# Doorbell.net
KiCad netlist of a schematic drawn in EAGLE
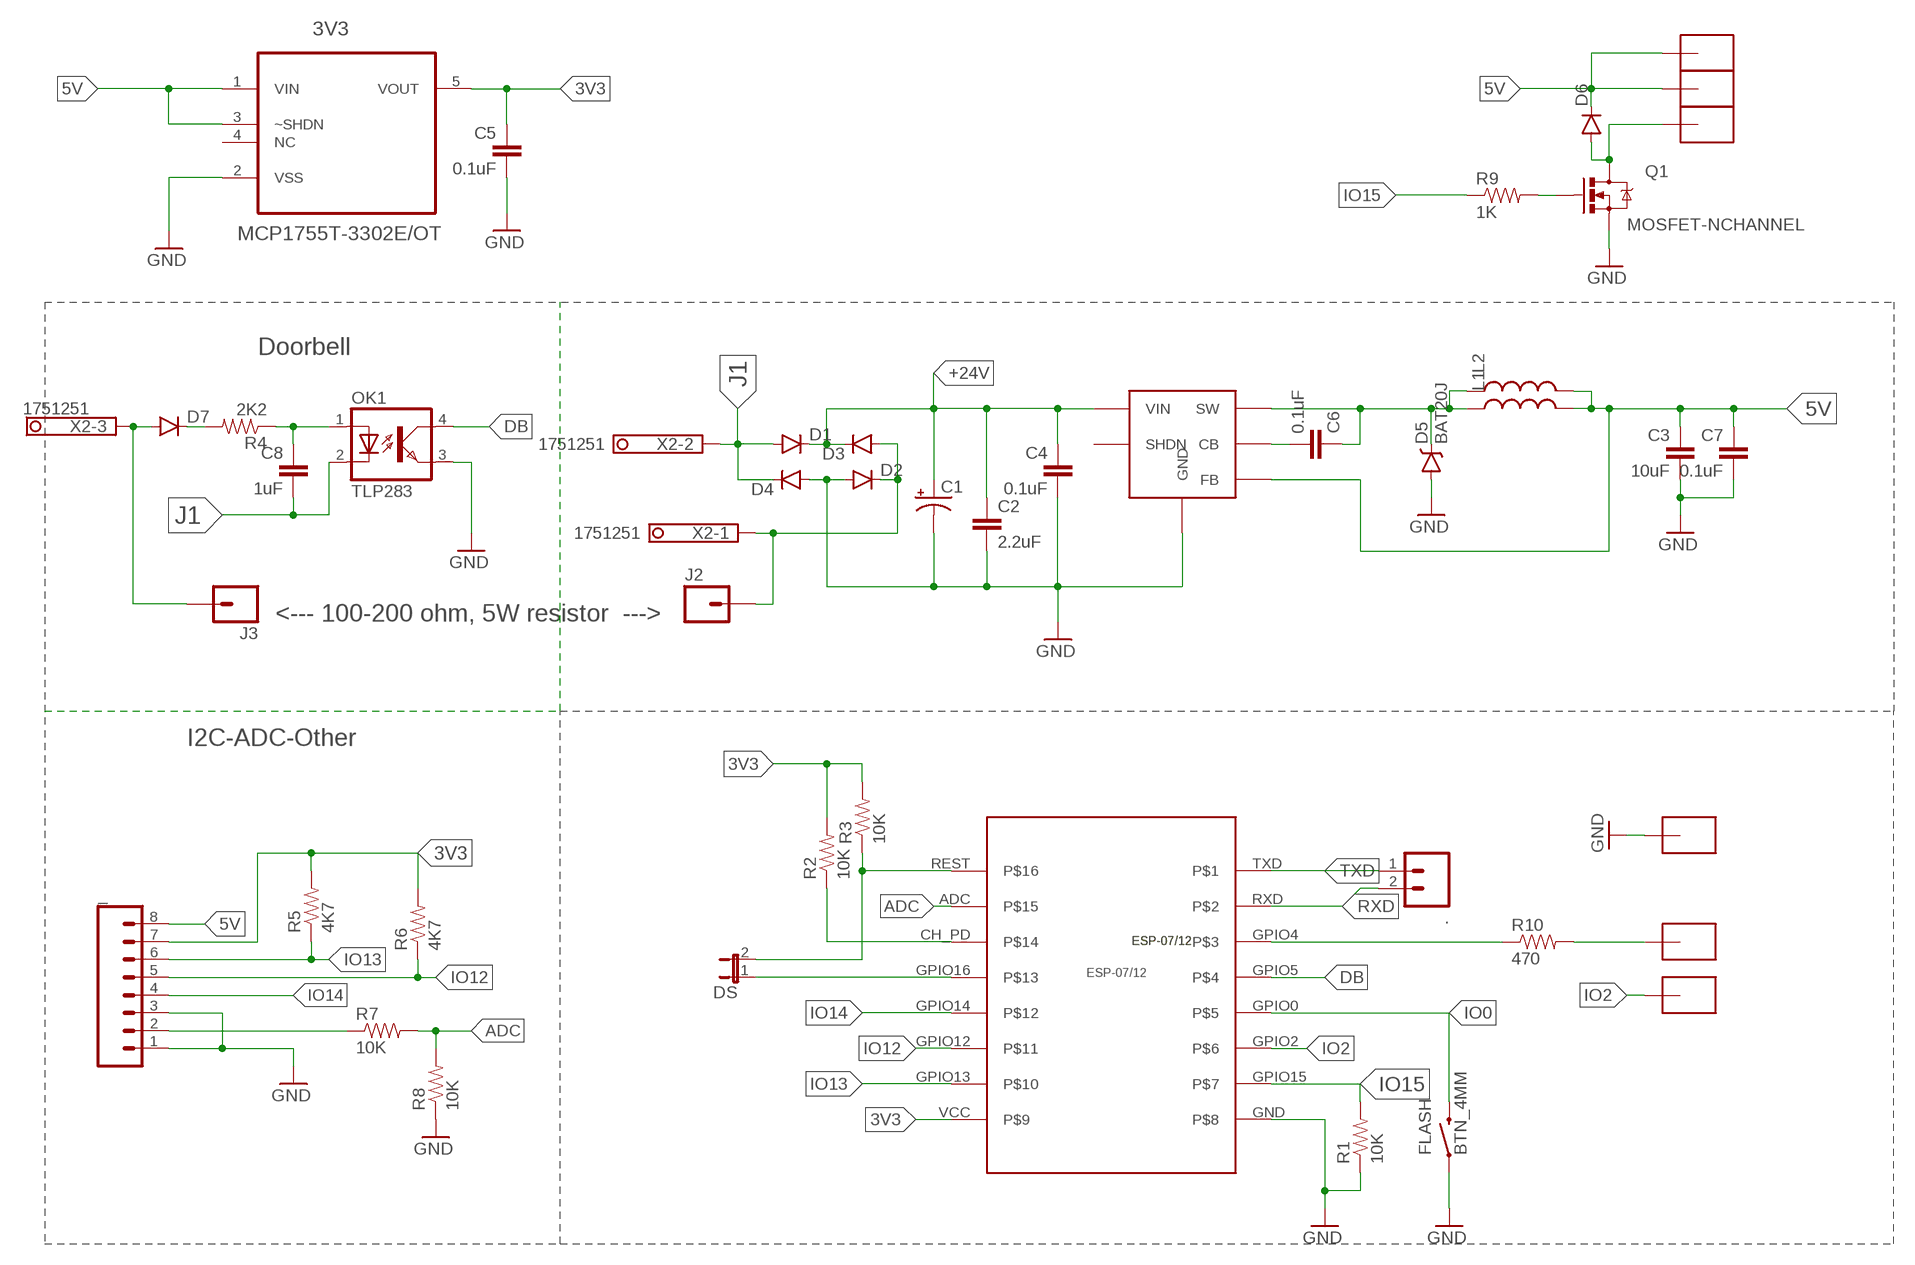
[diagram p0: schematic, sheet 1]

(export (version "E")
  (design (tool "Eeschema 10.0.6"))
  (components
    (comp (ref ".")
      (value "M02PTH")
      (footprint "eagle-import:1X02")
      (libsource (lib "eagle-import") (part "M02PTH"))
    )
    (comp (ref "3V3")
      (value "MCP1755T-3302E/OT")
      (footprint "eagle-import:SOT95P270X145-5N")
      (fields (field (name "MPN") "MCP1801T-3302I/OT"))
      (libsource (lib "eagle-import") (part "MCP1801T-3302I/OT"))
    )
    (comp (ref "C1")
      (value "CAP_POLPTH4")
      (footprint "eagle-import:CPOL-RADIAL-1000UF-25V")
      (libsource (lib "eagle-import") (part "CAP_POLPTH4"))
    )
    (comp (ref "C2")
      (value "2.2uF")
      (footprint "eagle-import:1206")
      (libsource (lib "eagle-import") (part "SparkFun-Passives_CAP1206"))
    )
    (comp (ref "C3")
      (value "10uF")
      (footprint "eagle-import:0805-CAP")
      (libsource (lib "eagle-import") (part "CAP"))
    )
    (comp (ref "C4")
      (value "0.1uF")
      (footprint "eagle-import:0805-CAP")
      (libsource (lib "eagle-import") (part "CAP"))
    )
    (comp (ref "C5")
      (value "0.1uF")
      (footprint "eagle-import:0805-CAP")
      (libsource (lib "eagle-import") (part "CAP"))
    )
    (comp (ref "C6")
      (value "0.1uF")
      (footprint "eagle-import:0805-CAP")
      (libsource (lib "eagle-import") (part "CAP"))
    )
    (comp (ref "C7")
      (value "0.1uF")
      (footprint "eagle-import:0805-CAP")
      (libsource (lib "eagle-import") (part "CAP"))
    )
    (comp (ref "C8")
      (value "1uF")
      (footprint "eagle-import:0805-CAP")
      (libsource (lib "eagle-import") (part "CAP"))
    )
    (comp (ref "D1")
      (value "DIODESOD123")
      (footprint "eagle-import:SOD-123")
      (libsource (lib "eagle-import") (part "DIODESOD123"))
    )
    (comp (ref "D2")
      (value "DIODESOD123")
      (footprint "eagle-import:SOD-123")
      (libsource (lib "eagle-import") (part "DIODESOD123"))
    )
    (comp (ref "D3")
      (value "DIODESOD123")
      (footprint "eagle-import:SOD-123")
      (libsource (lib "eagle-import") (part "DIODESOD123"))
    )
    (comp (ref "D4")
      (value "DIODESOD123")
      (footprint "eagle-import:SOD-123")
      (libsource (lib "eagle-import") (part "DIODESOD123"))
    )
    (comp (ref "D5")
      (value "BAT20J")
      (footprint "eagle-import:SOD-323")
      (libsource (lib "eagle-import") (part "DIODE-SCHOTTKY-BAT20J"))
    )
    (comp (ref "D6")
      (value "DIODESOD123")
      (footprint "eagle-import:SOD-123")
      (libsource (lib "eagle-import") (part "DIODESOD123"))
    )
    (comp (ref "D7")
      (value "DIODESOD123")
      (footprint "eagle-import:SOD-123")
      (libsource (lib "eagle-import") (part "DIODESOD123"))
    )
    (comp (ref "DS")
      (value "JUMPER-2SMD-NO")
      (footprint "eagle-import:SJ_2S-NO")
      (libsource (lib "eagle-import") (part "JUMPER-2SMD-NO"))
    )
    (comp (ref "FLASH")
      (value "BTN_4MM")
      (footprint "eagle-import:BTN_4MM")
      (libsource (lib "eagle-import") (part "BTN_4MM"))
    )
    (comp (ref "J2")
      (value "M01SMDNS")
      (footprint "eagle-import:1X01NS")
      (libsource (lib "eagle-import") (part "M01SMDNS"))
    )
    (comp (ref "J3")
      (value "M01SMDNS")
      (footprint "eagle-import:1X01NS")
      (libsource (lib "eagle-import") (part "M01SMDNS"))
    )
    (comp (ref "L1")
      (value "INDUCTOR0805")
      (footprint "eagle-import:0805")
      (libsource (lib "eagle-import") (part "INDUCTOR0805"))
    )
    (comp (ref "L2")
      (value "INDUCTOR0805")
      (footprint "eagle-import:0805")
      (libsource (lib "eagle-import") (part "INDUCTOR0805"))
    )
    (comp (ref "OK1")
      (value "TLP283")
      (footprint "eagle-import:MINI-FLAT-4")
      (libsource (lib "eagle-import") (part "TLP283"))
    )
    (comp (ref "Q1")
      (value "MOSFET-NCHANNEL")
      (footprint "eagle-import:SOT23-3")
      (libsource (lib "eagle-import") (part "MOSFET-NCHANNELAO3404A"))
    )
    (comp (ref "R1")
      (value "10K")
      (footprint "eagle-import:0805")
      (libsource (lib "eagle-import") (part "RESISTOR0805-RES"))
    )
    (comp (ref "R2")
      (value "10K")
      (footprint "eagle-import:0805")
      (libsource (lib "eagle-import") (part "RESISTOR0805-RES"))
    )
    (comp (ref "R3")
      (value "10K")
      (footprint "eagle-import:0805")
      (libsource (lib "eagle-import") (part "RESISTOR0805-RES"))
    )
    (comp (ref "R4")
      (value "2K2")
      (footprint "eagle-import:0805")
      (libsource (lib "eagle-import") (part "RESISTOR0805-RES"))
    )
    (comp (ref "R5")
      (value "4K7")
      (footprint "eagle-import:0805")
      (libsource (lib "eagle-import") (part "RESISTOR0805-RES"))
    )
    (comp (ref "R6")
      (value "4K7")
      (footprint "eagle-import:0805")
      (libsource (lib "eagle-import") (part "RESISTOR0805-RES"))
    )
    (comp (ref "R7")
      (value "10K")
      (footprint "eagle-import:0805")
      (libsource (lib "eagle-import") (part "RESISTOR0805-RES"))
    )
    (comp (ref "R8")
      (value "10K")
      (footprint "eagle-import:0805")
      (libsource (lib "eagle-import") (part "RESISTOR0805-RES"))
    )
    (comp (ref "R9")
      (value "1K")
      (footprint "eagle-import:0805")
      (libsource (lib "eagle-import") (part "RESISTOR0805-RES"))
    )
    (comp (ref "R10")
      (value "470")
      (footprint "eagle-import:0805")
      (libsource (lib "eagle-import") (part "RESISTOR0805-RES"))
    )
    (comp (ref "U$1")
      (value "ESP-07/12")
      (footprint "eagle-import:ESP-07_12")
      (libsource (lib "eagle-import") (part "ESP-07/12"))
    )
    (comp (ref "U$2")
      (value "SMD-PAD-SM")
      (footprint "eagle-import:SMD-PAD3")
      (libsource (lib "eagle-import") (part "SMD-PAD-SM"))
    )
    (comp (ref "U$3")
      (value "SMD-PAD-SM")
      (footprint "eagle-import:SMD-PAD3")
      (libsource (lib "eagle-import") (part "SMD-PAD-SM"))
    )
    (comp (ref "U$4")
      (value "SMD-PAD-SM")
      (footprint "eagle-import:SMD-PAD3")
      (libsource (lib "eagle-import") (part "SMD-PAD-SM"))
    )
    (comp (ref "U$5")
      (value "SMD-PAD-SM")
      (footprint "eagle-import:SMD-PAD3")
      (libsource (lib "eagle-import") (part "SMD-PAD-SM"))
    )
    (comp (ref "U$6")
      (value "SMD-PAD-SM")
      (footprint "eagle-import:SMD-PAD3")
      (libsource (lib "eagle-import") (part "SMD-PAD-SM"))
    )
    (comp (ref "U$7")
      (value "SMD-PAD-SM")
      (footprint "eagle-import:SMD-PAD3")
      (libsource (lib "eagle-import") (part "SMD-PAD-SM"))
    )
    (comp (ref "VREG")
      (value "LMR16006YQ5DDCRQ1")
      (footprint "eagle-import:SOT-23-6")
      (libsource (lib "eagle-import") (part "LMR16006YQ"))
    )
    (comp (ref "X2")
      (value "1751251")
      (footprint "eagle-import:1751251")
      (libsource (lib "eagle-import") (part "1751251"))
    )
    (comp (ref "_")
      (value "M08SILK_FEMALE_PTH")
      (footprint "eagle-import:1X08")
      (libsource (lib "eagle-import") (part "M08SILK_FEMALE_PTH"))
    )
  )
  (nets
    (net (code "1") (name "+24V") (class "Default")
      (node (ref "C1") (pin "+") (pinfunction "+_+") (pintype "passive"))
      (node (ref "C2") (pin "1") (pinfunction "1_1") (pintype "passive"))
      (node (ref "C4") (pin "1") (pinfunction "1_1") (pintype "passive"))
      (node (ref "D1") (pin "C") (pinfunction "C_C") (pintype "passive"))
      (node (ref "D3") (pin "C") (pinfunction "C_C") (pintype "passive"))
      (node (ref "VREG") (pin "5") (pinfunction "VIN_5") (pintype "input"))
    )
    (net (code "2") (name "3V3") (class "Default")
      (node (ref "3V3") (pin "5") (pinfunction "VOUT_5") (pintype "output"))
      (node (ref "C5") (pin "1") (pinfunction "1_1") (pintype "passive"))
      (node (ref "R2") (pin "2") (pinfunction "2_2") (pintype "passive"))
      (node (ref "R3") (pin "2") (pinfunction "2_2") (pintype "passive"))
      (node (ref "R5") (pin "2") (pinfunction "2_2") (pintype "passive"))
      (node (ref "R6") (pin "2") (pinfunction "2_2") (pintype "passive"))
      (node (ref "U$1") (pin "VCC") (pinfunction "P$9_VCC") (pintype "bidirectional"))
      (node (ref "_") (pin "7") (pinfunction "7_7") (pintype "passive"))
    )
    (net (code "3") (name "5V") (class "Default")
      (node (ref "3V3") (pin "1") (pinfunction "VIN_1") (pintype "power_in"))
      (node (ref "3V3") (pin "3") (pinfunction "~{SHDN}_3") (pintype "input"))
      (node (ref "C3") (pin "1") (pinfunction "1_1") (pintype "passive"))
      (node (ref "C7") (pin "1") (pinfunction "1_1") (pintype "passive"))
      (node (ref "D6") (pin "C") (pinfunction "C_C") (pintype "passive"))
      (node (ref "L1") (pin "2") (pinfunction "2_2") (pintype "passive"))
      (node (ref "L2") (pin "2") (pinfunction "2_2") (pintype "passive"))
      (node (ref "U$3") (pin "P$1") (pinfunction "P$1_P$1") (pintype "bidirectional"))
      (node (ref "U$7") (pin "P$1") (pinfunction "P$1_P$1") (pintype "bidirectional"))
      (node (ref "VREG") (pin "3") (pinfunction "FB_3") (pintype "input"))
      (node (ref "_") (pin "8") (pinfunction "8_8") (pintype "passive"))
    )
    (net (code "4") (name "ADC") (class "Default")
      (node (ref "R7") (pin "2") (pinfunction "2_2") (pintype "passive"))
      (node (ref "R8") (pin "2") (pinfunction "2_2") (pintype "passive"))
      (node (ref "U$1") (pin "ADC") (pinfunction "P$15_ADC") (pintype "bidirectional"))
    )
    (net (code "5") (name "DB") (class "Default")
      (node (ref "OK1") (pin "4") (pinfunction "COL_4") (pintype "passive"))
      (node (ref "U$1") (pin "GPIO5") (pinfunction "P$4_GPIO5") (pintype "bidirectional"))
    )
    (net (code "6") (name "GND") (class "Default")
      (node (ref "3V3") (pin "2") (pinfunction "VSS_2") (pintype "passive"))
      (node (ref "C1") (pin "-") (pinfunction "-_-") (pintype "passive"))
      (node (ref "C2") (pin "2") (pinfunction "2_2") (pintype "passive"))
      (node (ref "C3") (pin "2") (pinfunction "2_2") (pintype "passive"))
      (node (ref "C4") (pin "2") (pinfunction "2_2") (pintype "passive"))
      (node (ref "C5") (pin "2") (pinfunction "2_2") (pintype "passive"))
      (node (ref "C7") (pin "2") (pinfunction "2_2") (pintype "passive"))
      (node (ref "D2") (pin "A") (pinfunction "A_A") (pintype "passive"))
      (node (ref "D4") (pin "A") (pinfunction "A_A") (pintype "passive"))
      (node (ref "D5") (pin "A") (pinfunction "A_A") (pintype "passive"))
      (node (ref "FLASH") (pin "1") (pinfunction "1_1") (pintype "passive"))
      (node (ref "OK1") (pin "3") (pinfunction "EMIT_3") (pintype "passive"))
      (node (ref "Q1") (pin "2") (pinfunction "S_2") (pintype "passive"))
      (node (ref "R1") (pin "1") (pinfunction "1_1") (pintype "passive"))
      (node (ref "R8") (pin "1") (pinfunction "1_1") (pintype "passive"))
      (node (ref "U$1") (pin "GND") (pinfunction "P$8_GND") (pintype "bidirectional"))
      (node (ref "U$4") (pin "P$1") (pinfunction "P$1_P$1") (pintype "bidirectional"))
      (node (ref "VREG") (pin "2") (pinfunction "GND_2") (pintype "input"))
      (node (ref "_") (pin "1") (pinfunction "1_1") (pintype "passive"))
      (node (ref "_") (pin "3") (pinfunction "3_3") (pintype "passive"))
    )
    (net (code "7") (name "IO0") (class "Default")
      (node (ref "FLASH") (pin "2") (pinfunction "2_2") (pintype "passive"))
      (node (ref "U$1") (pin "GPIO0") (pinfunction "P$5_GPIO0") (pintype "bidirectional"))
    )
    (net (code "8") (name "IO2") (class "Default")
      (node (ref "U$1") (pin "GPIO2") (pinfunction "P$6_GPIO2") (pintype "bidirectional"))
      (node (ref "U$5") (pin "P$1") (pinfunction "P$1_P$1") (pintype "bidirectional"))
    )
    (net (code "9") (name "IO12") (class "Default")
      (node (ref "R6") (pin "1") (pinfunction "1_1") (pintype "passive"))
      (node (ref "U$1") (pin "GPIO12") (pinfunction "P$11_GPIO12") (pintype "bidirectional"))
      (node (ref "_") (pin "5") (pinfunction "5_5") (pintype "passive"))
    )
    (net (code "10") (name "IO13") (class "Default")
      (node (ref "R5") (pin "1") (pinfunction "1_1") (pintype "passive"))
      (node (ref "U$1") (pin "GPIO13") (pinfunction "P$10_GPIO13") (pintype "bidirectional"))
      (node (ref "_") (pin "6") (pinfunction "6_6") (pintype "passive"))
    )
    (net (code "11") (name "IO14") (class "Default")
      (node (ref "U$1") (pin "GPIO14") (pinfunction "P$12_GPIO14") (pintype "bidirectional"))
      (node (ref "_") (pin "4") (pinfunction "4_4") (pintype "passive"))
    )
    (net (code "12") (name "IO15") (class "Default")
      (node (ref "R1") (pin "2") (pinfunction "2_2") (pintype "passive"))
      (node (ref "R9") (pin "1") (pinfunction "1_1") (pintype "passive"))
      (node (ref "U$1") (pin "GPIO15") (pinfunction "P$7_GPIO15") (pintype "bidirectional"))
    )
    (net (code "13") (name "J1") (class "Default")
      (node (ref "C8") (pin "2") (pinfunction "2_2") (pintype "passive"))
      (node (ref "D1") (pin "A") (pinfunction "A_A") (pintype "passive"))
      (node (ref "D4") (pin "C") (pinfunction "C_C") (pintype "passive"))
      (node (ref "OK1") (pin "2") (pinfunction "C_2") (pintype "passive"))
      (node (ref "X2") (pin "2") (pinfunction "K_2") (pintype "passive"))
    )
    (net (code "14") (name "Net-(D7-PadC)") (class "Default")
      (node (ref "D7") (pin "C") (pinfunction "C_C") (pintype "passive"))
      (node (ref "R4") (pin "2") (pinfunction "2_2") (pintype "passive"))
    )
    (net (code "15") (name "Net-(OK1-A)") (class "Default")
      (node (ref "C8") (pin "1") (pinfunction "1_1") (pintype "passive"))
      (node (ref "OK1") (pin "1") (pinfunction "A_1") (pintype "passive"))
      (node (ref "R4") (pin "1") (pinfunction "1_1") (pintype "passive"))
    )
    (net (code "16") (name "Net-(Q1-D)") (class "Default")
      (node (ref "D6") (pin "A") (pinfunction "A_A") (pintype "passive"))
      (node (ref "Q1") (pin "3") (pinfunction "D_3") (pintype "passive"))
      (node (ref "U$6") (pin "P$1") (pinfunction "P$1_P$1") (pintype "bidirectional"))
    )
    (net (code "17") (name "Net-(Q1-G)") (class "Default")
      (node (ref "Q1") (pin "1") (pinfunction "G_1") (pintype "passive"))
      (node (ref "R9") (pin "2") (pinfunction "2_2") (pintype "passive"))
    )
    (net (code "18") (name "Net-(R7-Pad1)") (class "Default")
      (node (ref "R7") (pin "1") (pinfunction "1_1") (pintype "passive"))
      (node (ref "_") (pin "2") (pinfunction "2_2") (pintype "passive"))
    )
    (net (code "19") (name "Net-(R10-Pad2)") (class "Default")
      (node (ref "R10") (pin "2") (pinfunction "2_2") (pintype "passive"))
      (node (ref "U$2") (pin "P$1") (pinfunction "P$1_P$1") (pintype "bidirectional"))
    )
    (net (code "20") (name "Net-(U$1-P$3)") (class "Default")
      (node (ref "R10") (pin "1") (pinfunction "1_1") (pintype "passive"))
      (node (ref "U$1") (pin "GPIO4") (pinfunction "P$3_GPIO4") (pintype "bidirectional"))
    )
    (net (code "21") (name "Net-(U$1-P$13)") (class "Default")
      (node (ref "DS") (pin "1") (pinfunction "1_1") (pintype "passive"))
      (node (ref "U$1") (pin "GPIO16") (pinfunction "P$13_GPIO16") (pintype "bidirectional"))
    )
    (net (code "22") (name "Net-(U$1-P$14)") (class "Default")
      (node (ref "R2") (pin "1") (pinfunction "1_1") (pintype "passive"))
      (node (ref "U$1") (pin "CH_PD") (pinfunction "P$14_CH_PD") (pintype "bidirectional"))
    )
    (net (code "23") (name "Net-(U$1-P$16)") (class "Default")
      (node (ref "DS") (pin "2") (pinfunction "2_2") (pintype "passive"))
      (node (ref "R3") (pin "1") (pinfunction "1_1") (pintype "passive"))
      (node (ref "U$1") (pin "REST") (pinfunction "P$16_REST") (pintype "bidirectional"))
    )
    (net (code "24") (name "Net-(VREG-CB)") (class "Default")
      (node (ref "C6") (pin "2") (pinfunction "2_2") (pintype "passive"))
      (node (ref "VREG") (pin "1") (pinfunction "CB_1") (pintype "input"))
    )
    (net (code "25") (name "Net-(VREG-SW)") (class "Default")
      (node (ref "C6") (pin "1") (pinfunction "1_1") (pintype "passive"))
      (node (ref "D5") (pin "C") (pinfunction "C_C") (pintype "passive"))
      (node (ref "L1") (pin "1") (pinfunction "1_1") (pintype "passive"))
      (node (ref "L2") (pin "1") (pinfunction "1_1") (pintype "passive"))
      (node (ref "VREG") (pin "6") (pinfunction "SW_6") (pintype "output"))
    )
    (net (code "26") (name "Net-(X2A-K)") (class "Default")
      (node (ref "D2") (pin "C") (pinfunction "C_C") (pintype "passive"))
      (node (ref "D3") (pin "A") (pinfunction "A_A") (pintype "passive"))
      (node (ref "J2") (pin "1") (pinfunction "1_1") (pintype "passive"))
      (node (ref "X2") (pin "1") (pinfunction "K_1") (pintype "passive"))
    )
    (net (code "27") (name "Net-(X2C-K)") (class "Default")
      (node (ref "D7") (pin "A") (pinfunction "A_A") (pintype "passive"))
      (node (ref "J3") (pin "1") (pinfunction "1_1") (pintype "passive"))
      (node (ref "X2") (pin "3") (pinfunction "K_3") (pintype "passive"))
    )
    (net (code "28") (name "RXD") (class "Default")
      (node (ref ".") (pin "2") (pinfunction "2_2") (pintype "passive"))
      (node (ref "U$1") (pin "RXD") (pinfunction "P$2_RXD") (pintype "bidirectional"))
    )
    (net (code "29") (name "TXD") (class "Default")
      (node (ref ".") (pin "1") (pinfunction "1_1") (pintype "passive"))
      (node (ref "U$1") (pin "TXD") (pinfunction "P$1_TXD") (pintype "bidirectional"))
    )
    (net (code "30") (name "unconnected-(3V3-NC-Pad4)") (class "Default")
      (node (ref "3V3") (pin "4") (pinfunction "NC_4") (pintype "no_connect"))
    )
    (net (code "31") (name "unconnected-(VREG-SHDN-Pad4)") (class "Default")
      (node (ref "VREG") (pin "4") (pinfunction "SHDN_4") (pintype "input"))
    )
  )
)
